# POE.net
KiCad netlist of a schematic drawn in Altium Designer
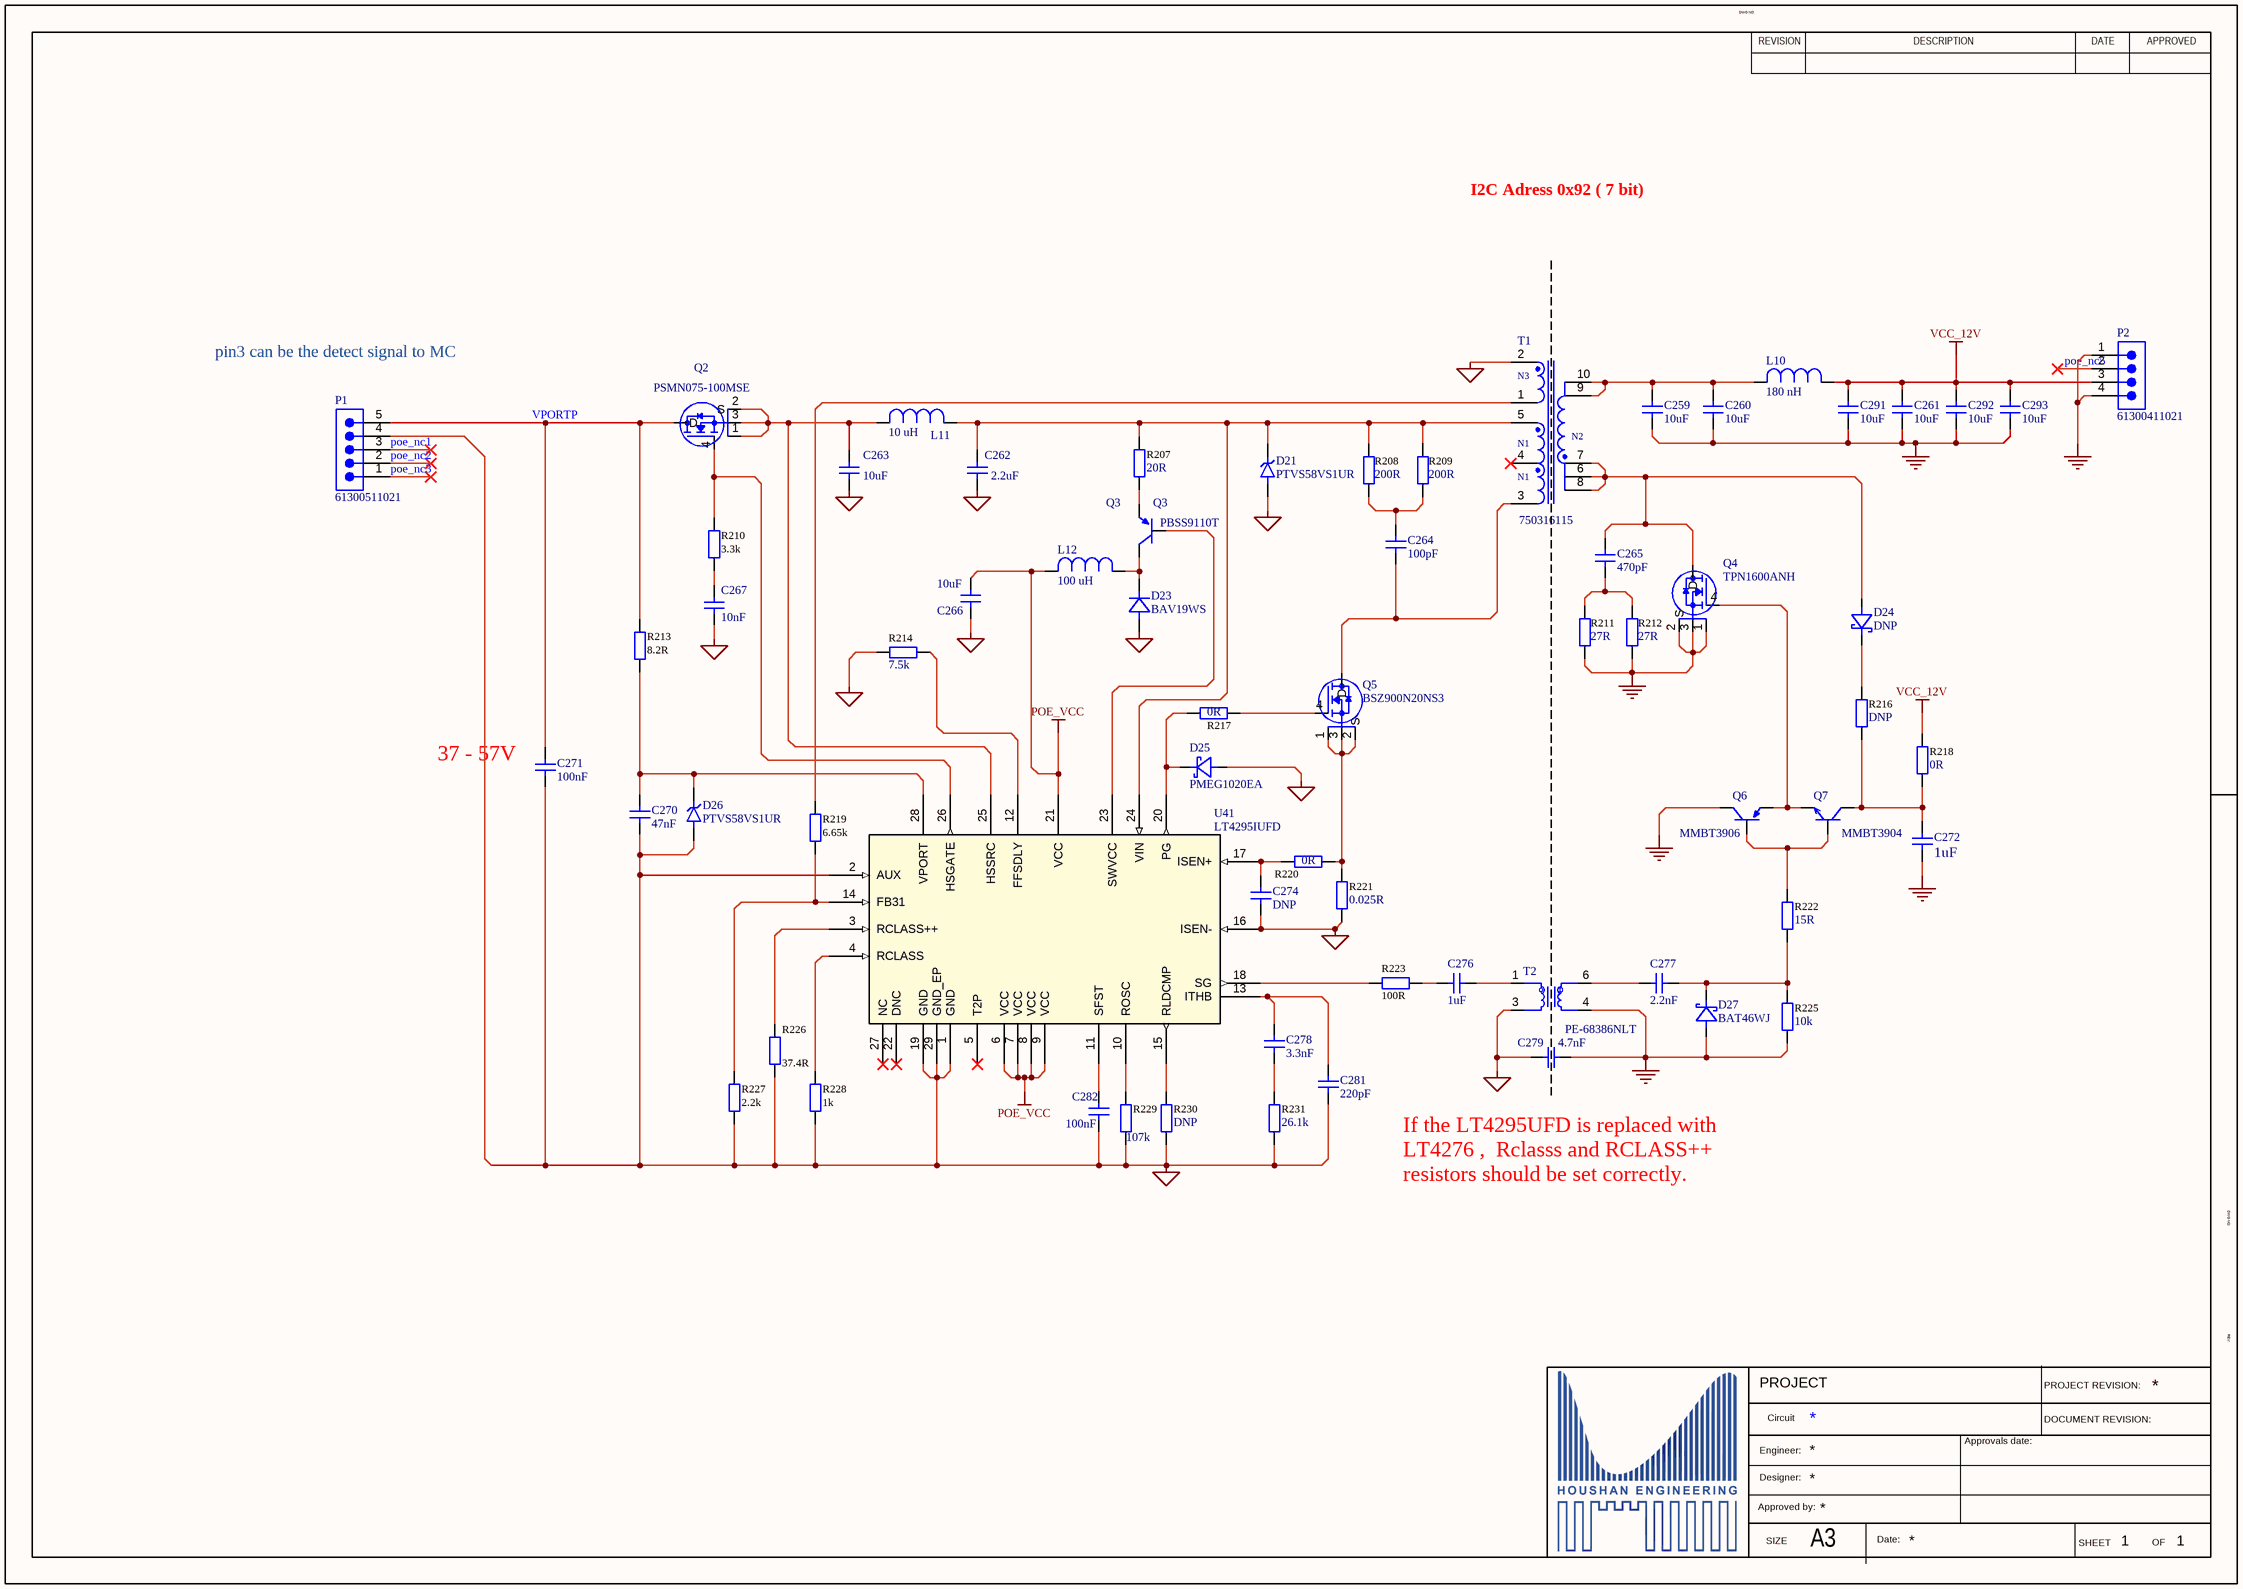
[diagram p0: POE.SchDoc]

(export (version "E")
  (design (tool "Eeschema 10.0.6"))
  (components
    (comp (ref "C259")
      (value "10uF")
      (footprint "C0805")
      (description "Multilayer Ceramic Capacitors MLCC - SMD/SMT 10uF 50V X5R C0805 10 %")
      (fields (field (name "PART NUMBER") "C0805_10uF_50V_10%_X5R") (field (name "TOLERANCE") "10%"))
      (libsource (lib "Database_Libs") (part "Cap"))
    )
    (comp (ref "C260")
      (value "10uF")
      (footprint "C0805")
      (description "Multilayer Ceramic Capacitors MLCC - SMD/SMT 10uF 50V X5R C0805 10 %")
      (fields (field (name "PART NUMBER") "C0805_10uF_50V_10%_X5R") (field (name "TOLERANCE") "10%"))
      (libsource (lib "Database_Libs") (part "Cap"))
    )
    (comp (ref "C261")
      (value "10uF")
      (footprint "C0805")
      (description "Multilayer Ceramic Capacitors MLCC - SMD/SMT 10uF 50V X5R C0805 10 %")
      (fields (field (name "PART NUMBER") "C0805_10uF_50V_10%_X5R") (field (name "TOLERANCE") "10%"))
      (libsource (lib "Database_Libs") (part "Cap"))
    )
    (comp (ref "C262")
      (value "2.2uF")
      (footprint "C1206")
      (description "Multilayer Ceramic Capacitors MLCC - SMD/SMT 2.2uF 100V X7R 1206 10%")
      (fields (field (name "PART NUMBER") "C1206_2.2uF_100V_10%_X7R") (field (name "TOLERANCE") "10%"))
      (libsource (lib "Database_Libs") (part "Cap"))
    )
    (comp (ref "C263")
      (value "10uF")
      (footprint "C1210")
      (description "Multilayer Ceramic Capacitors MLCC - SMD/SMT 10uF 100V X7S 1210 10%")
      (fields (field (name "PART NUMBER") "C1210_10uF_100V_10%_X7S") (field (name "TOLERANCE") "10%"))
      (libsource (lib "Database_Libs") (part "Cap"))
    )
    (comp (ref "C264")
      (value "100pF")
      (footprint "C1206")
      (description "Multilayer Ceramic Capacitors MLCC - SMD/SMT 100pF 630V U2J 1206 5%")
      (fields (field (name "PART NUMBER") "C1206_100pF_630V_5%_U2J") (field (name "TOLERANCE") "5%"))
      (libsource (lib "Database_Libs") (part "Cap"))
    )
    (comp (ref "C265")
      (value "470pF")
      (footprint "C1206")
      (description "Multilayer Ceramic Capacitors MLCC - SMD/SMT 470pF 630V U2J 1206 5%")
      (fields (field (name "PART NUMBER") "C1206_470pF_630V_5%_U2J") (field (name "TOLERANCE") "5%"))
      (libsource (lib "Database_Libs") (part "Cap"))
    )
    (comp (ref "C266")
      (value "10uF")
      (footprint "C1206")
      (description "Multilayer Ceramic Capacitors MLCC - SMD/SMT 10uF 25V X7R 1206  10%")
      (fields (field (name "PART NUMBER") "C1206_10uF_25V_10%_X7R") (field (name "TOLERANCE") "10%"))
      (libsource (lib "Database_Libs") (part "Cap"))
    )
    (comp (ref "C267")
      (value "10nF")
      (footprint "C0603")
      (description "Multilayer Ceramic Capacitors MLCC - SMD/SMT 0.01uF 100V X7R 0603 10%")
      (fields (field (name "PART NUMBER") "C0603_10nF_100V_10%_X7R") (field (name "TOLERANCE") "10%"))
      (libsource (lib "Database_Libs") (part "Cap"))
    )
    (comp (ref "C270")
      (value "47nF")
      (footprint "C0603")
      (description "Multilayer Ceramic Capacitors MLCC - SMD/SMT 0.047uF 100V X7R 0603 20%")
      (fields (field (name "PART NUMBER") "C0603_47nF_100V_20%_X7R") (field (name "TOLERANCE") "20%"))
      (libsource (lib "Database_Libs") (part "Cap"))
    )
    (comp (ref "C271")
      (value "100nF")
      (footprint "C0603")
      (description "Multilayer Ceramic Capacitors MLCC - SMD/SMT 0.1uF 25V X7R 0603 10%")
      (fields (field (name "PART NUMBER") "C0603_100nF_100V_10%_X7R") (field (name "TOLERANCE") "10%"))
      (libsource (lib "Database_Libs") (part "Cap"))
    )
    (comp (ref "C272")
      (value "1uF")
      (footprint "C0805")
      (description "Multilayer Ceramic Capacitors MLCC - SMD/SMT 1uF 25V X7R 0805 10%")
      (fields (field (name "PART NUMBER") "C0805_1uF_25V_10%_X7R") (field (name "TOLERANCE") "10%"))
      (libsource (lib "Database_Libs") (part "Cap"))
    )
    (comp (ref "C274")
      (value "DNP")
      (footprint "C0402")
      (description "Multilayer Ceramic Capacitors MLCC - SMD/SMT 10nF 100V X5R C0402 20 %")
      (fields (field (name "PART NUMBER") "C0402_10nF_100V_20%_X5R") (field (name "TOLERANCE") "20%"))
      (libsource (lib "Database_Libs") (part "Cap"))
    )
    (comp (ref "C276")
      (value "1uF")
      (footprint "C0603")
      (description "Multilayer Ceramic Capacitors MLCC - SMD/SMT 1uF 25V X7R 0603 10%")
      (fields (field (name "PART NUMBER") "C0603_1uF_25V_10%_X7R") (field (name "TOLERANCE") "10%"))
      (libsource (lib "Database_Libs") (part "Cap"))
    )
    (comp (ref "C277")
      (value "2.2nF")
      (footprint "C0603")
      (description "Multilayer Ceramic Capacitors MLCC - SMD/SMT 2200pF 25V X7R 0603 10%")
      (fields (field (name "PART NUMBER") "C0603_2.2nF_25V_10%_X7R") (field (name "TOLERANCE") "10%"))
      (libsource (lib "Database_Libs") (part "Cap"))
    )
    (comp (ref "C278")
      (value "3.3nF")
      (footprint "C0603")
      (description "Multilayer Ceramic Capacitors MLCC - SMD/SMT 3300pF 25V X7R 0603 10%")
      (fields (field (name "PART NUMBER") "C0603_3.3nF_25V_10%_X7R") (field (name "TOLERANCE") "10%"))
      (libsource (lib "Database_Libs") (part "Cap"))
    )
    (comp (ref "C279")
      (value "4.7nF")
      (footprint "C1812")
      (description "Multilayer Ceramic Capacitors MLCC - SMD/SMT 4700pF 2kV X7R 1812 10%")
      (fields (field (name "PART NUMBER") "C1812_4.7nF_2kV_10%_X7R") (field (name "TOLERANCE") "10%"))
      (libsource (lib "Database_Libs") (part "Cap"))
    )
    (comp (ref "C281")
      (value "220pF")
      (footprint "C0603")
      (description "Multilayer Ceramic Capacitors MLCC - SMD/SMT 220pF 25V X7R 0603 10%")
      (fields (field (name "PART NUMBER") "C0603_220pF_25V_10%_X7R") (field (name "TOLERANCE") "10%"))
      (libsource (lib "Database_Libs") (part "Cap"))
    )
    (comp (ref "C282")
      (value "100nF")
      (footprint "C0603")
      (description "Multilayer Ceramic Capacitors MLCC - SMD/SMT 0.1uF 25V X7R 0603 10%")
      (fields (field (name "PART NUMBER") "C0603_100nF_100V_10%_X7R") (field (name "TOLERANCE") "10%"))
      (libsource (lib "Database_Libs") (part "Cap"))
    )
    (comp (ref "C291")
      (value "10uF")
      (footprint "C0805")
      (description "Multilayer Ceramic Capacitors MLCC - SMD/SMT 10uF 50V X5R C0805 10 %")
      (fields (field (name "PART NUMBER") "C0805_10uF_50V_10%_X5R") (field (name "TOLERANCE") "10%"))
      (libsource (lib "Database_Libs") (part "Cap"))
    )
    (comp (ref "C292")
      (value "10uF")
      (footprint "C0805")
      (description "Multilayer Ceramic Capacitors MLCC - SMD/SMT 10uF 50V X5R C0805 10 %")
      (fields (field (name "PART NUMBER") "C0805_10uF_50V_10%_X5R") (field (name "TOLERANCE") "10%"))
      (libsource (lib "Database_Libs") (part "Cap"))
    )
    (comp (ref "C293")
      (value "10uF")
      (footprint "C0805")
      (description "Multilayer Ceramic Capacitors MLCC - SMD/SMT 10uF 50V X5R C0805 10 %")
      (fields (field (name "PART NUMBER") "C0805_10uF_50V_10%_X5R") (field (name "TOLERANCE") "10%"))
      (libsource (lib "Database_Libs") (part "Cap"))
    )
    (comp (ref "D21")
      (value "PTVS58VS1UR")
      (footprint "SOD123W")
      (description "ESD Protection Diodes / TVS Diodes PTVS58VS1UR/SOD123W/SOD2")
      (fields (field (name "MP") "MMSZ5252BS-7-F") (field (name "MANUFACTURER") "NEXPERIA"))
      (libsource (lib "Database_Libs") (part "Zener"))
    )
    (comp (ref "D23")
      (value "BAV19WS")
      (footprint "SOD323")
      (description "Small Signal Switching Diodes 120V 250mW")
      (fields
        (field (name "MANUFACTURER") "Diodes Inc.")
        (field (name "MANUFACTURER PART NUMBER") "BAV19WS-7-F")
      )
      (libsource (lib "Database_Libs") (part "Diode"))
    )
    (comp (ref "D24")
      (value "DNP")
      (footprint "SOD323")
      (description "Schottky 40V")
      (fields (field (name "PART NUMBER") "Schottky_DNP"))
      (libsource (lib "Database_Libs") (part "Schottky"))
    )
    (comp (ref "D25")
      (value "PMEG1020EA")
      (footprint "SOD323")
      (description "Schottky Diodes & Rectifiers PMEG1020EA/SOD323/SOD2")
      (fields (field (name "MANUFACTURER") "Nexperia"))
      (libsource (lib "Database_Libs") (part "Schottky"))
    )
    (comp (ref "D26")
      (value "PTVS58VS1UR")
      (footprint "SOD123W")
      (description "ESD Protection Diodes / TVS Diodes PTVS58VS1UR/SOD123W/SOD2")
      (fields (field (name "MP") "MMSZ5252BS-7-F") (field (name "MANUFACTURER") "NEXPERIA"))
      (libsource (lib "Database_Libs") (part "Zener"))
    )
    (comp (ref "D27")
      (value "BAT46WJ")
      (footprint "SOD323F")
      (description "100 V, Schottky Diodes & Rectifiers BAT46WJ/SOD323F/SOD323F")
      (fields
        (field (name "MANUFACTURER") "Nexperia")
        (field (name "MANUFACTURER PART NUMBER") "BAT46WJ,115")
      )
      (libsource (lib "Database_Libs") (part "Schottky"))
    )
    (comp (ref "L10")
      (value "180 nH")
      (footprint "IND_DO1813H_COC")
      (description "Power Inductors - SMD 180nH Unshld 20% 10A 3mOhms")
      (fields (field (name "PART NUMBER") "DO1813H-181") (field (name "MANUFACTURER") "Coilcraft"))
      (libsource (lib "Database_Libs") (part "Inductor"))
    )
    (comp (ref "L11")
      (value "10 uH")
      (footprint "IND_DO1607B_COC")
      (description "Power Inductors - SMD 10uH Shld 20% 1.5A 160mOhms")
      (fields (field (name "PART NUMBER") "DO1608C-103") (field (name "MANUFACTURER") "Coilcraft"))
      (libsource (lib "Database_Libs") (part "Inductor"))
    )
    (comp (ref "L12")
      (value "100 uH")
      (footprint "IND_DO1607B_COC")
      (description "Power Inductors - SMD 10uH Shld 20% 1.5A 160mOhms")
      (fields (field (name "PART NUMBER") "DO1608C-104") (field (name "MANUFACTURER") "Coilcraft"))
      (libsource (lib "Database_Libs") (part "Inductor"))
    )
    (comp (ref "P1")
      (value "61300511021")
      (footprint "61300511021")
      (fields (field (name "MANUFACTURER") "Wurth Electronics"))
      (libsource (lib "Database_Libs") (part "Pinheader_5P"))
    )
    (comp (ref "P2")
      (value "61300411021")
      (footprint "61300411021")
      (fields (field (name "MANUFACTURER") "Wurth Electronics"))
      (libsource (lib "Database_Libs") (part "Pinheader_4P"))
    )
    (comp (ref "Q2")
      (value "PSMN075-100MSE")
      (footprint "SOT1210")
      (description "N-Channel 100V 18A (Tj) 65W (Tc) Surface Mount LFPAK33")
      (fields (field (name "PART NUMBER") "PSMN075-100MSEX") (field (name "MANUFACTURER") "NEXPERIA"))
      (libsource (lib "Database_Libs") (part "N-CH_MOSFET"))
    )
    (comp (ref "Q3")
      (value "PBSS9110T")
      (footprint "SOT23")
      (description "Trans GP BJT PNP 100V 300mW 1 A 3-Pin SOT-23")
      (fields (field (name "MANUFACTURER") "NEXPERIA"))
      (libsource (lib "Database_Libs") (part "BJT_PNP"))
    )
    (comp (ref "Q4")
      (value "TPN1600ANH")
      (footprint "SOT1210")
      (description "Silicon N-channel MOS, 100V, 18A")
      (fields (field (name "MANUFACTURER") "Toshiba"))
      (libsource (lib "Database_Libs") (part "N-CH_MOSFET"))
    )
    (comp (ref "Q5")
      (value "BSZ900N20NS3")
      (footprint "SOT1210")
      (description "MOSFETs N-Ch 200V 15.2A TDSON-8 OptiMOS 3")
      (fields
        (field (name "MANUFACTURER") "Infineon")
        (field (name "MANUFACTURER PART NUMBER") "BSZ900N20NS3GATMA1")
      )
      (libsource (lib "Database_Libs") (part "N-CH_MOSFET"))
    )
    (comp (ref "Q6")
      (value "MMBT3906")
      (footprint "SOT23")
      (description "Trans GP BJT PNP 40V 3-Pin SOT-23")
      (fields (field (name "MANUFACTURER") "NEXPERIA"))
      (libsource (lib "Database_Libs") (part "BJT_PNP"))
    )
    (comp (ref "Q7")
      (value "MMBT3904")
      (footprint "SOT23")
      (description "Trans GP BJT NPN 40V 3-Pin SOT-23")
      (fields (field (name "MANUFACTURER") "NEXPERIA"))
      (libsource (lib "Database_Libs") (part "BJT_NPN"))
    )
    (comp (ref "R207")
      (value "20R")
      (footprint "R0805")
      (description "resistor")
      (fields (field (name "PART NUMBER") "R0805_20R_1%_62.5mW_100PPM_150V") (field (name "TOLERANCE") "1%"))
      (libsource (lib "Database_Libs") (part "Resistor"))
    )
    (comp (ref "R208")
      (value "200R")
      (footprint "R1206")
      (description "resistor")
      (fields (field (name "PART NUMBER") "R1206_200R_1%_250mW_100PPM_200V") (field (name "TOLERANCE") "1%"))
      (libsource (lib "Database_Libs") (part "Resistor"))
    )
    (comp (ref "R209")
      (value "200R")
      (footprint "R1206")
      (description "resistor")
      (fields (field (name "PART NUMBER") "R1206_200R_1%_250mW_100PPM_200V") (field (name "TOLERANCE") "1%"))
      (libsource (lib "Database_Libs") (part "Resistor"))
    )
    (comp (ref "R210")
      (value "3.3k")
      (footprint "R0603")
      (description "resistor")
      (fields (field (name "PART NUMBER") "R0603_3.3k_1%_62.5mW_100PPM_75V") (field (name "TOLERANCE") "1%"))
      (libsource (lib "Database_Libs") (part "Resistor"))
    )
    (comp (ref "R211")
      (value "27R")
      (footprint "R1206")
      (description "resistor")
      (fields (field (name "PART NUMBER") "R1206_27R_1%_250mW_100PPM_200V") (field (name "TOLERANCE") "1%"))
      (libsource (lib "Database_Libs") (part "Resistor"))
    )
    (comp (ref "R212")
      (value "27R")
      (footprint "R1206")
      (description "resistor")
      (fields (field (name "PART NUMBER") "R1206_27R_1%_250mW_100PPM_200V") (field (name "TOLERANCE") "1%"))
      (libsource (lib "Database_Libs") (part "Resistor"))
    )
    (comp (ref "R213")
      (value "8.2R")
      (footprint "R0805")
      (description "resistor")
      (fields (field (name "PART NUMBER") "R0805_8.2R_1%_62.5mW_100PPM_150V") (field (name "TOLERANCE") "1%"))
      (libsource (lib "Database_Libs") (part "Resistor"))
    )
    (comp (ref "R214")
      (value "7.5k")
      (footprint "R0603")
      (description "resistor")
      (fields (field (name "PART NUMBER") "R0603_7.5k_1%_62.5mW_100PPM_75V") (field (name "TOLERANCE") "1%"))
      (libsource (lib "") (part "Resistor_2"))
    )
    (comp (ref "R216")
      (value "DNP")
      (footprint "R0805")
      (description "resistor")
      (fields (field (name "PART NUMBER") "R0805_1k_1%_62.5mW_100PPM_150V") (field (name "TOLERANCE") "1%"))
      (libsource (lib "Database_Libs") (part "Resistor"))
    )
    (comp (ref "R217")
      (value "0R")
      (footprint "R0603")
      (description "resistor")
      (fields (field (name "PART NUMBER") "R0603_0R_1%_62.5mW_100PPM_75V") (field (name "TOLERANCE") "1%"))
      (libsource (lib "") (part "Resistor_2"))
    )
    (comp (ref "R218")
      (value "0R")
      (footprint "R0805")
      (description "resistor")
      (fields (field (name "PART NUMBER") "R0805_0R_1%_62.5mW_100PPM_150V") (field (name "TOLERANCE") "1%"))
      (libsource (lib "Database_Libs") (part "Resistor"))
    )
    (comp (ref "R219")
      (value "6.65k")
      (footprint "R0603")
      (description "resistor")
      (fields (field (name "PART NUMBER") "R0603_6.65k_1%_62.5mW_100PPM_75V") (field (name "TOLERANCE") "1%"))
      (libsource (lib "Database_Libs") (part "Resistor"))
    )
    (comp (ref "R220")
      (value "0R")
      (footprint "R0603")
      (description "resistor")
      (fields (field (name "PART NUMBER") "R0603_0R_1%_62.5mW_100PPM_75V") (field (name "TOLERANCE") "1%"))
      (libsource (lib "") (part "Resistor_2"))
    )
    (comp (ref "R221")
      (value "0.025R")
      (footprint "R1206")
      (description "resistor")
      (fields
        (field (name "PART NUMBER") "R1206_0.025R_1%_250mW_100PPM_200V")
        (field (name "TOLERANCE") "1%")
      )
      (libsource (lib "Database_Libs") (part "Resistor"))
    )
    (comp (ref "R222")
      (value "15R")
      (footprint "R0603")
      (description "resistor")
      (fields (field (name "PART NUMBER") "R0603_15R_1%_62.5mW_100PPM_75V") (field (name "TOLERANCE") "1%"))
      (libsource (lib "Database_Libs") (part "Resistor"))
    )
    (comp (ref "R223")
      (value "100R")
      (footprint "R0603")
      (description "resistor")
      (fields (field (name "PART NUMBER") "R0603_100R_1%_62.5mW_100PPM_75V") (field (name "TOLERANCE") "1%"))
      (libsource (lib "") (part "Resistor_1"))
    )
    (comp (ref "R225")
      (value "10k")
      (footprint "R0603")
      (description "resistor")
      (fields (field (name "PART NUMBER") "R0603_10k_1%_62.5mW_100PPM_75V") (field (name "TOLERANCE") "1%"))
      (libsource (lib "Database_Libs") (part "Resistor"))
    )
    (comp (ref "R226")
      (value "37.4R")
      (footprint "R0805")
      (description "resistor")
      (fields
        (field (name "PART NUMBER") "R0805_37.4R_1%_62.5mW_100PPM_150V")
        (field (name "TOLERANCE") "1%")
      )
      (libsource (lib "Database_Libs") (part "Resistor"))
    )
    (comp (ref "R227")
      (value "2.2k")
      (footprint "R0603")
      (description "resistor")
      (fields (field (name "PART NUMBER") "R0603_2.2k_1%_62.5mW_100PPM_75V") (field (name "TOLERANCE") "1%"))
      (libsource (lib "Database_Libs") (part "Resistor"))
    )
    (comp (ref "R228")
      (value "1k")
      (footprint "R0805")
      (description "resistor")
      (fields (field (name "PART NUMBER") "R0805_1k_1%_62.5mW_100PPM_150V") (field (name "TOLERANCE") "1%"))
      (libsource (lib "Database_Libs") (part "Resistor"))
    )
    (comp (ref "R229")
      (value "107k")
      (footprint "R0603")
      (description "resistor")
      (fields (field (name "PART NUMBER") "R0603_107k_1%_62.5mW_100PPM_75V") (field (name "TOLERANCE") "1%"))
      (libsource (lib "Database_Libs") (part "Resistor"))
    )
    (comp (ref "R230")
      (value "DNP")
      (footprint "R0603")
      (description "resistor")
      (fields (field (name "PART NUMBER") "R0603_51k_1%_62.5mW_100PPM_75V") (field (name "TOLERANCE") "1%"))
      (libsource (lib "Database_Libs") (part "Resistor"))
    )
    (comp (ref "R231")
      (value "26.1k")
      (footprint "R0603")
      (description "resistor")
      (fields (field (name "PART NUMBER") "R0603_26.1k_1%_62.5mW_100PPM_75V") (field (name "TOLERANCE") "1%"))
      (libsource (lib "Database_Libs") (part "Resistor"))
    )
    (comp (ref "T1")
      (value "750316115")
      (footprint "WE-PoE+_EP13_L17.75W13.46H12.7")
      (description "Flyback trnsformer 12V 3A, 2:1")
      (fields (field (name "MANUFACTURER") "Wurth Elektronik"))
      (libsource (lib "Database_Libs") (part "750316115"))
    )
    (comp (ref "T2")
      (value "PE-68386NLT")
      (footprint "SOP254P864X249-6N")
      (description "785ÂµH Pulse Transformer 1:1 Surface Mount")
      (fields (field (name "MANUFACTURER") "Pulse Electronics"))
      (libsource (lib "Database_Libs") (part "PE-68386NL"))
    )
    (comp (ref "U41")
      (value "LT4295IUFD")
      (footprint "QFN-29_UFD")
      (description "Power Switch ICs - POE/LAN IEEE 802.3bt PD Int w/ For/Fly Cntr")
      (fields
        (field (name "MANUFACTURER") "Analog Device")
        (field (name "MANUFACTURER PART NUMBER") "LT4295IUFD#TRPBF")
      )
      (libsource (lib "Database_Libs") (part "LT4295IUFDTRPBF"))
    )
  )
  (nets
    (net (code "1") (name "/VPORTP") (class "Default")
      (node (ref "C271") (pin "2") (pinfunction "2_2") (pintype "passive"))
      (node (ref "P1") (pin "5") (pinfunction "5_5") (pintype "passive"))
      (node (ref "Q2") (pin "MB") (pinfunction "D_MB") (pintype "passive"))
      (node (ref "R213") (pin "2") (pinfunction "2_2") (pintype "passive"))
    )
    (net (code "2") (name "/poe_nc1") (class "Default")
      (node (ref "P1") (pin "3") (pinfunction "3_3") (pintype "passive+no_connect"))
    )
    (net (code "3") (name "/poe_nc2") (class "Default")
      (node (ref "P1") (pin "2") (pinfunction "2_2") (pintype "passive+no_connect"))
    )
    (net (code "4") (name "/poe_nc3") (class "Default")
      (node (ref "P1") (pin "1") (pinfunction "1_1") (pintype "passive+no_connect"))
    )
    (net (code "5") (name "/poe_nc5") (class "Default")
      (node (ref "P2") (pin "2") (pinfunction "2_2") (pintype "passive+no_connect"))
    )
    (net (code "6") (name "GND") (class "Default")
      (node (ref "C259") (pin "1") (pinfunction "1_1") (pintype "passive"))
      (node (ref "C260") (pin "1") (pinfunction "1_1") (pintype "passive"))
      (node (ref "C261") (pin "1") (pinfunction "1_1") (pintype "passive"))
      (node (ref "C272") (pin "2") (pinfunction "2_2") (pintype "passive"))
      (node (ref "C279") (pin "1") (pinfunction "1_1") (pintype "passive"))
      (node (ref "C291") (pin "1") (pinfunction "1_1") (pintype "passive"))
      (node (ref "C292") (pin "1") (pinfunction "1_1") (pintype "passive"))
      (node (ref "C293") (pin "1") (pinfunction "1_1") (pintype "passive"))
      (node (ref "D27") (pin "2") (pinfunction "A_2") (pintype "passive"))
      (node (ref "P2") (pin "1") (pinfunction "1_1") (pintype "passive"))
      (node (ref "P2") (pin "4") (pinfunction "4_4") (pintype "passive"))
      (node (ref "Q4") (pin "1") (pinfunction "S_1") (pintype "passive"))
      (node (ref "Q4") (pin "2") (pinfunction "S_2") (pintype "passive"))
      (node (ref "Q4") (pin "3") (pinfunction "S_3") (pintype "passive"))
      (node (ref "Q6") (pin "3") (pinfunction "C_3") (pintype "passive"))
      (node (ref "R211") (pin "1") (pinfunction "1_1") (pintype "passive"))
      (node (ref "R212") (pin "1") (pinfunction "1_1") (pintype "passive"))
      (node (ref "R225") (pin "1") (pinfunction "1_1") (pintype "passive"))
      (node (ref "T2") (pin "4") (pinfunction "4_4") (pintype "passive"))
    )
    (net (code "7") (name "Net-(C259-Pad2)") (class "Default")
      (node (ref "C259") (pin "2") (pinfunction "2_2") (pintype "passive"))
      (node (ref "C260") (pin "2") (pinfunction "2_2") (pintype "passive"))
      (node (ref "L10") (pin "2") (pinfunction "2_2") (pintype "passive"))
      (node (ref "T1") (pin "10") (pinfunction "10_10") (pintype "passive"))
      (node (ref "T1") (pin "9") (pinfunction "9_9") (pintype "passive"))
    )
    (net (code "8") (name "Net-(C264-Pad2)") (class "Default")
      (node (ref "C264") (pin "2") (pinfunction "2_2") (pintype "passive"))
      (node (ref "R208") (pin "1") (pinfunction "1_1") (pintype "passive"))
      (node (ref "R209") (pin "1") (pinfunction "1_1") (pintype "passive"))
    )
    (net (code "9") (name "Net-(C265-Pad1)") (class "Default")
      (node (ref "C265") (pin "1") (pinfunction "1_1") (pintype "passive"))
      (node (ref "R211") (pin "2") (pinfunction "2_2") (pintype "passive"))
      (node (ref "R212") (pin "2") (pinfunction "2_2") (pintype "passive"))
    )
    (net (code "10") (name "Net-(C267-Pad2)") (class "Default")
      (node (ref "C267") (pin "2") (pinfunction "2_2") (pintype "passive"))
      (node (ref "R210") (pin "1") (pinfunction "1_1") (pintype "passive"))
    )
    (net (code "11") (name "Net-(C276-Pad1)") (class "Default")
      (node (ref "C276") (pin "1") (pinfunction "1_1") (pintype "passive"))
      (node (ref "T2") (pin "1") (pinfunction "1_1") (pintype "passive"))
    )
    (net (code "12") (name "Net-(C276-Pad2)") (class "Default")
      (node (ref "C276") (pin "2") (pinfunction "2_2") (pintype "passive"))
      (node (ref "R223") (pin "2") (pinfunction "2_2") (pintype "passive"))
    )
    (net (code "13") (name "Net-(C277-Pad2)") (class "Default")
      (node (ref "C277") (pin "2") (pinfunction "2_2") (pintype "passive"))
      (node (ref "T2") (pin "6") (pinfunction "6_6") (pintype "passive"))
    )
    (net (code "14") (name "Net-(C278-Pad1)") (class "Default")
      (node (ref "C278") (pin "1") (pinfunction "1_1") (pintype "passive"))
      (node (ref "R231") (pin "2") (pinfunction "2_2") (pintype "passive"))
    )
    (net (code "15") (name "Net-(D21-K)") (class "Default")
      (node (ref "C262") (pin "2") (pinfunction "2_2") (pintype "passive"))
      (node (ref "D21") (pin "1") (pinfunction "K_1") (pintype "passive"))
      (node (ref "L11") (pin "1") (pinfunction "1_1") (pintype "passive"))
      (node (ref "R207") (pin "2") (pinfunction "2_2") (pintype "passive"))
      (node (ref "R208") (pin "2") (pinfunction "2_2") (pintype "passive"))
      (node (ref "R209") (pin "2") (pinfunction "2_2") (pintype "passive"))
      (node (ref "T1") (pin "5") (pinfunction "5_5") (pintype "passive"))
      (node (ref "U41") (pin "24") (pinfunction "VIN_24") (pintype "input"))
    )
    (net (code "16") (name "Net-(D23-K)") (class "Default")
      (node (ref "D23") (pin "1") (pinfunction "K_1") (pintype "passive"))
      (node (ref "L12") (pin "1") (pinfunction "1_1") (pintype "passive"))
      (node (ref "Q3") (pin "3") (pinfunction "C_3") (pintype "passive"))
    )
    (net (code "17") (name "Net-(D24-A)") (class "Default")
      (node (ref "C265") (pin "2") (pinfunction "2_2") (pintype "passive"))
      (node (ref "D24") (pin "2") (pinfunction "A_2") (pintype "passive"))
      (node (ref "Q4") (pin "MB") (pinfunction "D_MB") (pintype "passive"))
      (node (ref "T1") (pin "6") (pinfunction "6_6") (pintype "passive"))
      (node (ref "T1") (pin "7") (pinfunction "7_7") (pintype "passive"))
      (node (ref "T1") (pin "8") (pinfunction "8_8") (pintype "passive"))
    )
    (net (code "18") (name "Net-(D24-K)") (class "Default")
      (node (ref "D24") (pin "1") (pinfunction "K_1") (pintype "passive"))
      (node (ref "R216") (pin "2") (pinfunction "2_2") (pintype "passive"))
    )
    (net (code "19") (name "Net-(D25-K)") (class "Default")
      (node (ref "D25") (pin "1") (pinfunction "K_1") (pintype "passive"))
      (node (ref "R217") (pin "2") (pinfunction "2_2") (pintype "passive"))
      (node (ref "U41") (pin "20") (pinfunction "PG_20") (pintype "output"))
    )
    (net (code "20") (name "Net-(D26-K)") (class "Default")
      (node (ref "C270") (pin "2") (pinfunction "2_2") (pintype "passive"))
      (node (ref "D26") (pin "1") (pinfunction "K_1") (pintype "passive"))
      (node (ref "R213") (pin "1") (pinfunction "1_1") (pintype "passive"))
      (node (ref "U41") (pin "28") (pinfunction "VPORT_28") (pintype "passive"))
    )
    (net (code "21") (name "Net-(D27-K)") (class "Default")
      (node (ref "C277") (pin "1") (pinfunction "1_1") (pintype "passive"))
      (node (ref "D27") (pin "1") (pinfunction "K_1") (pintype "passive"))
      (node (ref "R222") (pin "1") (pinfunction "1_1") (pintype "passive"))
      (node (ref "R225") (pin "2") (pinfunction "2_2") (pintype "passive"))
    )
    (net (code "22") (name "Net-(Q2-G)") (class "Default")
      (node (ref "Q2") (pin "4") (pinfunction "G_4") (pintype "passive"))
      (node (ref "R210") (pin "2") (pinfunction "2_2") (pintype "passive"))
      (node (ref "U41") (pin "26") (pinfunction "HSGATE_26") (pintype "output"))
    )
    (net (code "23") (name "Net-(Q3-B)") (class "Default")
      (node (ref "Q3") (pin "1") (pinfunction "B_1") (pintype "passive"))
      (node (ref "U41") (pin "23") (pinfunction "SWVCC_23") (pintype "power_in"))
    )
    (net (code "24") (name "Net-(Q3-E)") (class "Default")
      (node (ref "Q3") (pin "2") (pinfunction "E_2") (pintype "passive"))
      (node (ref "R207") (pin "1") (pinfunction "1_1") (pintype "passive"))
    )
    (net (code "25") (name "Net-(Q4-G)") (class "Default")
      (node (ref "Q4") (pin "4") (pinfunction "G_4") (pintype "passive"))
      (node (ref "Q6") (pin "2") (pinfunction "E_2") (pintype "passive"))
      (node (ref "Q7") (pin "2") (pinfunction "E_2") (pintype "passive"))
    )
    (net (code "26") (name "Net-(Q5-D)") (class "Default")
      (node (ref "C264") (pin "1") (pinfunction "1_1") (pintype "passive"))
      (node (ref "Q5") (pin "MB") (pinfunction "D_MB") (pintype "passive"))
      (node (ref "T1") (pin "3") (pinfunction "3_3") (pintype "passive"))
    )
    (net (code "27") (name "Net-(Q5-G)") (class "Default")
      (node (ref "Q5") (pin "4") (pinfunction "G_4") (pintype "passive"))
      (node (ref "R217") (pin "1") (pinfunction "1_1") (pintype "passive"))
    )
    (net (code "28") (name "Net-(Q5-S-Pad1)") (class "Default")
      (node (ref "Q5") (pin "1") (pinfunction "S_1") (pintype "passive"))
      (node (ref "Q5") (pin "2") (pinfunction "S_2") (pintype "passive"))
      (node (ref "Q5") (pin "3") (pinfunction "S_3") (pintype "passive"))
      (node (ref "R220") (pin "1") (pinfunction "1_1") (pintype "passive"))
      (node (ref "R221") (pin "2") (pinfunction "2_2") (pintype "passive"))
    )
    (net (code "29") (name "Net-(Q6-B)") (class "Default")
      (node (ref "Q6") (pin "1") (pinfunction "B_1") (pintype "passive"))
      (node (ref "Q7") (pin "1") (pinfunction "B_1") (pintype "passive"))
      (node (ref "R222") (pin "2") (pinfunction "2_2") (pintype "passive"))
    )
    (net (code "30") (name "Net-(Q7-C)") (class "Default")
      (node (ref "C272") (pin "1") (pinfunction "1_1") (pintype "passive"))
      (node (ref "Q7") (pin "3") (pinfunction "C_3") (pintype "passive"))
      (node (ref "R216") (pin "1") (pinfunction "1_1") (pintype "passive"))
      (node (ref "R218") (pin "1") (pinfunction "1_1") (pintype "passive"))
    )
    (net (code "31") (name "Net-(R219-Pad2)") (class "Default")
      (node (ref "R219") (pin "2") (pinfunction "2_2") (pintype "passive"))
      (node (ref "T1") (pin "1") (pinfunction "1_1") (pintype "passive"))
    )
    (net (code "32") (name "Net-(U41-FB31)") (class "Default")
      (node (ref "R219") (pin "1") (pinfunction "1_1") (pintype "passive"))
      (node (ref "R227") (pin "2") (pinfunction "2_2") (pintype "passive"))
      (node (ref "U41") (pin "14") (pinfunction "FB31_14") (pintype "input"))
    )
    (net (code "33") (name "Net-(U41-FFSDLY)") (class "Default")
      (node (ref "R214") (pin "1") (pinfunction "1_1") (pintype "passive"))
      (node (ref "U41") (pin "12") (pinfunction "FFSDLY_12") (pintype "passive"))
    )
    (net (code "34") (name "Net-(U41-HSSRC)") (class "Default")
      (node (ref "C263") (pin "2") (pinfunction "2_2") (pintype "passive"))
      (node (ref "L11") (pin "2") (pinfunction "2_2") (pintype "passive"))
      (node (ref "Q2") (pin "1") (pinfunction "S_1") (pintype "passive"))
      (node (ref "Q2") (pin "2") (pinfunction "S_2") (pintype "passive"))
      (node (ref "Q2") (pin "3") (pinfunction "S_3") (pintype "passive"))
      (node (ref "U41") (pin "25") (pinfunction "HSSRC_25") (pintype "passive"))
    )
    (net (code "35") (name "Net-(U41-ISEN+)") (class "Default")
      (node (ref "C274") (pin "2") (pinfunction "2_2") (pintype "passive"))
      (node (ref "R220") (pin "2") (pinfunction "2_2") (pintype "passive"))
      (node (ref "U41") (pin "17") (pinfunction "ISEN+_17") (pintype "input"))
    )
    (net (code "36") (name "Net-(U41-ITHB)") (class "Default")
      (node (ref "C278") (pin "2") (pinfunction "2_2") (pintype "passive"))
      (node (ref "C281") (pin "1") (pinfunction "1_1") (pintype "passive"))
      (node (ref "U41") (pin "13") (pinfunction "ITHB_13") (pintype "passive"))
    )
    (net (code "37") (name "Net-(U41-RCLASS)") (class "Default")
      (node (ref "R228") (pin "2") (pinfunction "2_2") (pintype "passive"))
      (node (ref "U41") (pin "4") (pinfunction "RCLASS_4") (pintype "input"))
    )
    (net (code "38") (name "Net-(U41-RCLASS++)") (class "Default")
      (node (ref "R226") (pin "2") (pinfunction "2_2") (pintype "passive"))
      (node (ref "U41") (pin "3") (pinfunction "RCLASS++_3") (pintype "input"))
    )
    (net (code "39") (name "Net-(U41-RLDCMP)") (class "Default")
      (node (ref "R230") (pin "2") (pinfunction "2_2") (pintype "passive"))
      (node (ref "U41") (pin "15") (pinfunction "RLDCMP_15") (pintype "output"))
    )
    (net (code "40") (name "Net-(U41-ROSC)") (class "Default")
      (node (ref "R229") (pin "2") (pinfunction "2_2") (pintype "passive"))
      (node (ref "U41") (pin "10") (pinfunction "ROSC_10") (pintype "passive"))
    )
    (net (code "41") (name "Net-(U41-SFST)") (class "Default")
      (node (ref "C282") (pin "2") (pinfunction "2_2") (pintype "passive"))
      (node (ref "U41") (pin "11") (pinfunction "SFST_11") (pintype "passive"))
    )
    (net (code "42") (name "Net-(U41-SG)") (class "Default")
      (node (ref "R223") (pin "1") (pinfunction "1_1") (pintype "passive"))
      (node (ref "U41") (pin "18") (pinfunction "SG_18") (pintype "output"))
    )
    (net (code "43") (name "POE_GND") (class "Default")
      (node (ref "C262") (pin "1") (pinfunction "1_1") (pintype "passive"))
      (node (ref "C263") (pin "1") (pinfunction "1_1") (pintype "passive"))
      (node (ref "C266") (pin "1") (pinfunction "1_1") (pintype "passive"))
      (node (ref "C267") (pin "1") (pinfunction "1_1") (pintype "passive"))
      (node (ref "C270") (pin "1") (pinfunction "1_1") (pintype "passive"))
      (node (ref "C271") (pin "1") (pinfunction "1_1") (pintype "passive"))
      (node (ref "C274") (pin "1") (pinfunction "1_1") (pintype "passive"))
      (node (ref "C279") (pin "2") (pinfunction "2_2") (pintype "passive"))
      (node (ref "C281") (pin "2") (pinfunction "2_2") (pintype "passive"))
      (node (ref "C282") (pin "1") (pinfunction "1_1") (pintype "passive"))
      (node (ref "D21") (pin "2") (pinfunction "A_2") (pintype "passive"))
      (node (ref "D23") (pin "2") (pinfunction "A_2") (pintype "passive"))
      (node (ref "D25") (pin "2") (pinfunction "A_2") (pintype "passive"))
      (node (ref "D26") (pin "2") (pinfunction "A_2") (pintype "passive"))
      (node (ref "P1") (pin "4") (pinfunction "4_4") (pintype "passive"))
      (node (ref "R214") (pin "2") (pinfunction "2_2") (pintype "passive"))
      (node (ref "R221") (pin "1") (pinfunction "1_1") (pintype "passive"))
      (node (ref "R226") (pin "1") (pinfunction "1_1") (pintype "passive"))
      (node (ref "R227") (pin "1") (pinfunction "1_1") (pintype "passive"))
      (node (ref "R228") (pin "1") (pinfunction "1_1") (pintype "passive"))
      (node (ref "R229") (pin "1") (pinfunction "1_1") (pintype "passive"))
      (node (ref "R230") (pin "1") (pinfunction "1_1") (pintype "passive"))
      (node (ref "R231") (pin "1") (pinfunction "1_1") (pintype "passive"))
      (node (ref "T1") (pin "2") (pinfunction "2_2") (pintype "passive"))
      (node (ref "T2") (pin "3") (pinfunction "3_3") (pintype "passive"))
      (node (ref "U41") (pin "1") (pinfunction "GND_1") (pintype "power_in"))
      (node (ref "U41") (pin "16") (pinfunction "ISEN-_16") (pintype "input"))
      (node (ref "U41") (pin "19") (pinfunction "GND_19") (pintype "power_in"))
      (node (ref "U41") (pin "2") (pinfunction "AUX_2") (pintype "input"))
      (node (ref "U41") (pin "29") (pinfunction "GND_EP_29") (pintype "power_in"))
    )
    (net (code "44") (name "POE_VCC") (class "Default")
      (node (ref "C266") (pin "2") (pinfunction "2_2") (pintype "passive"))
      (node (ref "L12") (pin "2") (pinfunction "2_2") (pintype "passive"))
      (node (ref "U41") (pin "21") (pinfunction "VCC_21") (pintype "power_in"))
      (node (ref "U41") (pin "6") (pinfunction "VCC_6") (pintype "power_in"))
      (node (ref "U41") (pin "7") (pinfunction "VCC_7") (pintype "power_in"))
      (node (ref "U41") (pin "8") (pinfunction "VCC_8") (pintype "power_in"))
      (node (ref "U41") (pin "9") (pinfunction "VCC_9") (pintype "power_in"))
    )
    (net (code "45") (name "VCC_12V") (class "Default")
      (node (ref "C261") (pin "2") (pinfunction "2_2") (pintype "passive"))
      (node (ref "C291") (pin "2") (pinfunction "2_2") (pintype "passive"))
      (node (ref "C292") (pin "2") (pinfunction "2_2") (pintype "passive"))
      (node (ref "C293") (pin "2") (pinfunction "2_2") (pintype "passive"))
      (node (ref "L10") (pin "1") (pinfunction "1_1") (pintype "passive"))
      (node (ref "P2") (pin "3") (pinfunction "3_3") (pintype "passive"))
      (node (ref "R218") (pin "2") (pinfunction "2_2") (pintype "passive"))
    )
    (net (code "46") (name "unconnected-(T1-Pad4)") (class "Default")
      (node (ref "T1") (pin "4") (pinfunction "4_4") (pintype "passive+no_connect"))
    )
    (net (code "47") (name "unconnected-(U41-DNC-Pad22)") (class "Default")
      (node (ref "U41") (pin "22") (pinfunction "DNC_22") (pintype "passive+no_connect"))
    )
    (net (code "48") (name "unconnected-(U41-NC-Pad27)") (class "Default")
      (node (ref "U41") (pin "27") (pinfunction "NC_27") (pintype "passive+no_connect"))
    )
    (net (code "49") (name "unconnected-(U41-T2P-Pad5)") (class "Default")
      (node (ref "U41") (pin "5") (pinfunction "T2P_5") (pintype "passive+no_connect"))
    )
  )
)
